# rev1.net
KiCad netlist of a schematic drawn in EAGLE
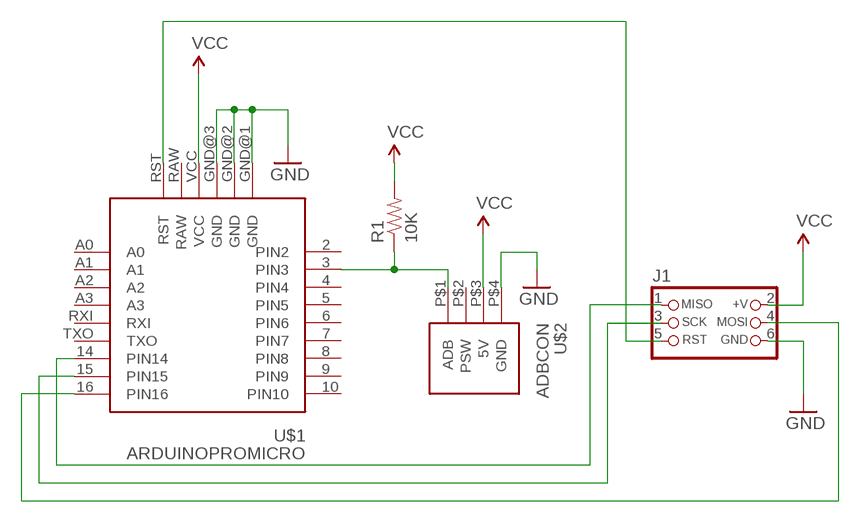
[diagram p0: schematic, sheet 1]

(export (version "E")
  (design (tool "Eeschema 10.0.6"))
  (components
    (comp (ref "J1")
      (value "CON_HEADER_PRG_AVR_ICSP-PTH")
      (footprint "eagle-import:HEADER_PRG_2X03")
      (libsource (lib "eagle-import") (part "CON_HEADER_PRG_AVR_ICSP-PTH"))
    )
    (comp (ref "R1")
      (value "10K")
      (footprint "eagle-import:1206")
      (libsource (lib "eagle-import") (part "RESISTOR1206"))
    )
    (comp (ref "U$1")
      (value "ARDUINOPROMICRO")
      (footprint "eagle-import:DIP")
      (libsource (lib "eagle-import") (part "ARDUINOPROMICRO"))
    )
    (comp (ref "U$2")
      (value "ADBCON")
      (footprint "eagle-import:ADBCON")
      (libsource (lib "eagle-import") (part "ADBCON"))
    )
  )
  (nets
    (net (code "1") (name "GND") (class "Default")
      (node (ref "J1") (pin "6") (pinfunction "GND_6") (pintype "passive"))
      (node (ref "U$1") (pin "GND@1") (pinfunction "GND_GND@1") (pintype "bidirectional"))
      (node (ref "U$1") (pin "GND@2") (pinfunction "GND_GND@2") (pintype "bidirectional"))
      (node (ref "U$1") (pin "GND@3") (pinfunction "GND_GND@3") (pintype "bidirectional"))
      (node (ref "U$2") (pin "P$4") (pinfunction "GND_P$4") (pintype "bidirectional"))
    )
    (net (code "2") (name "Net-(J1-MISO)") (class "Default")
      (node (ref "J1") (pin "1") (pinfunction "MISO_1") (pintype "passive"))
      (node (ref "U$1") (pin "14") (pinfunction "PIN14_14") (pintype "bidirectional"))
    )
    (net (code "3") (name "Net-(J1-MOSI)") (class "Default")
      (node (ref "J1") (pin "4") (pinfunction "MOSI_4") (pintype "passive"))
      (node (ref "U$1") (pin "16") (pinfunction "PIN16_16") (pintype "bidirectional"))
    )
    (net (code "4") (name "Net-(J1-RST)") (class "Default")
      (node (ref "J1") (pin "5") (pinfunction "RST_5") (pintype "passive"))
      (node (ref "U$1") (pin "RST") (pinfunction "RST_RST") (pintype "bidirectional"))
    )
    (net (code "5") (name "Net-(J1-SCK)") (class "Default")
      (node (ref "J1") (pin "3") (pinfunction "SCK_3") (pintype "passive"))
      (node (ref "U$1") (pin "15") (pinfunction "PIN15_15") (pintype "bidirectional"))
    )
    (net (code "6") (name "Net-(U$1-PIN3)") (class "Default")
      (node (ref "R1") (pin "1") (pinfunction "1_1") (pintype "passive"))
      (node (ref "U$1") (pin "3") (pinfunction "PIN3_3") (pintype "bidirectional"))
      (node (ref "U$2") (pin "P$1") (pinfunction "ADB_P$1") (pintype "bidirectional"))
    )
    (net (code "7") (name "VCC") (class "Default")
      (node (ref "J1") (pin "2") (pinfunction "+V_2") (pintype "passive"))
      (node (ref "R1") (pin "2") (pinfunction "2_2") (pintype "passive"))
      (node (ref "U$1") (pin "VCC") (pinfunction "VCC_VCC") (pintype "bidirectional"))
      (node (ref "U$2") (pin "P$3") (pinfunction "5V_P$3") (pintype "bidirectional"))
    )
    (net (code "8") (name "unconnected-(U$1-PIN2-Pad2)") (class "Default")
      (node (ref "U$1") (pin "2") (pinfunction "PIN2_2") (pintype "bidirectional"))
    )
    (net (code "9") (name "unconnected-(U$1-PIN4-Pad4)") (class "Default")
      (node (ref "U$1") (pin "4") (pinfunction "PIN4_4") (pintype "bidirectional"))
    )
    (net (code "10") (name "unconnected-(U$1-PIN5-Pad5)") (class "Default")
      (node (ref "U$1") (pin "5") (pinfunction "PIN5_5") (pintype "bidirectional"))
    )
    (net (code "11") (name "unconnected-(U$1-PIN6-Pad6)") (class "Default")
      (node (ref "U$1") (pin "6") (pinfunction "PIN6_6") (pintype "bidirectional"))
    )
    (net (code "12") (name "unconnected-(U$1-PIN7-Pad7)") (class "Default")
      (node (ref "U$1") (pin "7") (pinfunction "PIN7_7") (pintype "bidirectional"))
    )
    (net (code "13") (name "unconnected-(U$1-PIN8-Pad8)") (class "Default")
      (node (ref "U$1") (pin "8") (pinfunction "PIN8_8") (pintype "bidirectional"))
    )
    (net (code "14") (name "unconnected-(U$1-PIN9-Pad9)") (class "Default")
      (node (ref "U$1") (pin "9") (pinfunction "PIN9_9") (pintype "bidirectional"))
    )
    (net (code "15") (name "unconnected-(U$1-PIN10-Pad10)") (class "Default")
      (node (ref "U$1") (pin "10") (pinfunction "PIN10_10") (pintype "bidirectional"))
    )
    (net (code "16") (name "unconnected-(U$1-PadA0)") (class "Default")
      (node (ref "U$1") (pin "A0") (pinfunction "A0_A0") (pintype "bidirectional"))
    )
    (net (code "17") (name "unconnected-(U$1-PadA1)") (class "Default")
      (node (ref "U$1") (pin "A1") (pinfunction "A1_A1") (pintype "bidirectional"))
    )
    (net (code "18") (name "unconnected-(U$1-PadA2)") (class "Default")
      (node (ref "U$1") (pin "A2") (pinfunction "A2_A2") (pintype "bidirectional"))
    )
    (net (code "19") (name "unconnected-(U$1-PadA3)") (class "Default")
      (node (ref "U$1") (pin "A3") (pinfunction "A3_A3") (pintype "bidirectional"))
    )
    (net (code "20") (name "unconnected-(U$1-PadRAW)") (class "Default")
      (node (ref "U$1") (pin "RAW") (pinfunction "RAW_RAW") (pintype "bidirectional"))
    )
    (net (code "21") (name "unconnected-(U$1-PadRXI)") (class "Default")
      (node (ref "U$1") (pin "RXI") (pinfunction "RXI_RXI") (pintype "bidirectional"))
    )
    (net (code "22") (name "unconnected-(U$1-PadTXO)") (class "Default")
      (node (ref "U$1") (pin "TXO") (pinfunction "TXO_TXO") (pintype "bidirectional"))
    )
    (net (code "23") (name "unconnected-(U$2-PSW-PadP$2)") (class "Default")
      (node (ref "U$2") (pin "P$2") (pinfunction "PSW_P$2") (pintype "bidirectional"))
    )
  )
)
